# 50k-celebration-pcb.net
KiCad netlist of a schematic drawn in EAGLE
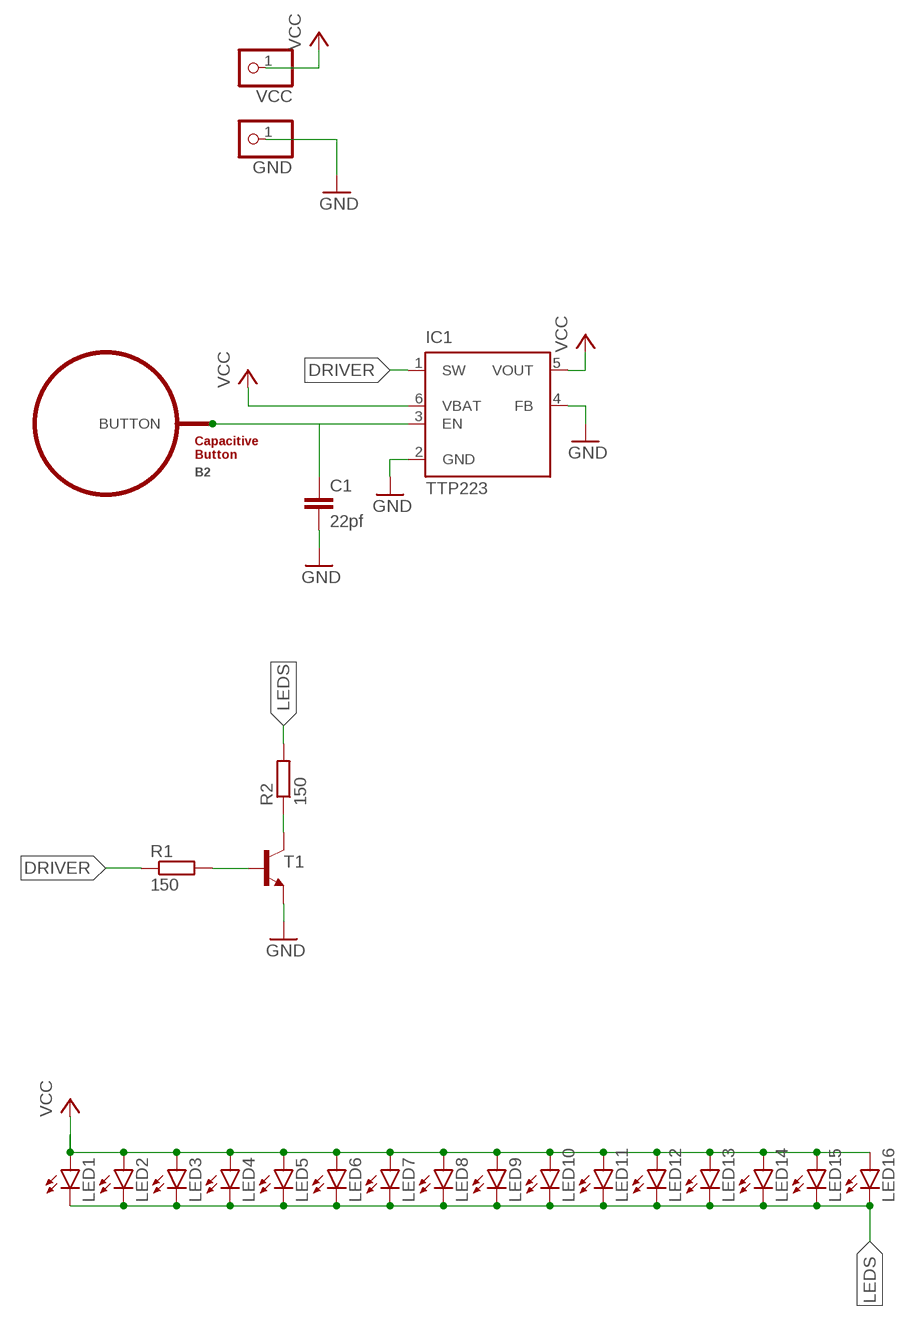
[diagram p0: schematic, sheet 1]

(export (version "E")
  (design (tool "Eeschema 10.0.6"))
  (components
    (comp (ref "B2")
      (value "BUTTON_PASSIVE8MM")
      (footprint "eagle-import:BUTTON_PASSIVE_8MM")
      (libsource (lib "eagle-import") (part "BUTTON_PASSIVE8MM"))
    )
    (comp (ref "C1")
      (value "22pf")
      (footprint "eagle-import:C0805")
      (libsource (lib "eagle-import") (part "C-EUC0805"))
    )
    (comp (ref "GND")
      (value "WPAD-1-SQ-0.5MM")
      (footprint "eagle-import:WPAD-1-SQ-0.5MM")
      (libsource (lib "eagle-import") (part "WPAD-1-SQ-0.5MM"))
    )
    (comp (ref "IC1")
      (value "TTP223")
      (footprint "eagle-import:TSOT23-6_DDC")
      (fields (field (name "MPN") "TPS61070DDCR"))
      (libsource (lib "eagle-import") (part "TPS6107DDC0"))
    )
    (comp (ref "LED1")
      (value "LEDCHIP-LED0805")
      (footprint "eagle-import:CHIP-LED0805")
      (libsource (lib "eagle-import") (part "LEDCHIP-LED0805"))
    )
    (comp (ref "LED2")
      (value "LEDCHIP-LED0805")
      (footprint "eagle-import:CHIP-LED0805")
      (libsource (lib "eagle-import") (part "LEDCHIP-LED0805"))
    )
    (comp (ref "LED3")
      (value "LEDCHIP-LED0805")
      (footprint "eagle-import:CHIP-LED0805")
      (libsource (lib "eagle-import") (part "LEDCHIP-LED0805"))
    )
    (comp (ref "LED4")
      (value "LEDCHIP-LED0805")
      (footprint "eagle-import:CHIP-LED0805")
      (libsource (lib "eagle-import") (part "LEDCHIP-LED0805"))
    )
    (comp (ref "LED5")
      (value "LEDCHIP-LED0805")
      (footprint "eagle-import:CHIP-LED0805")
      (libsource (lib "eagle-import") (part "LEDCHIP-LED0805"))
    )
    (comp (ref "LED6")
      (value "LEDCHIP-LED0805")
      (footprint "eagle-import:CHIP-LED0805")
      (libsource (lib "eagle-import") (part "LEDCHIP-LED0805"))
    )
    (comp (ref "LED7")
      (value "LEDCHIP-LED0805")
      (footprint "eagle-import:CHIP-LED0805")
      (libsource (lib "eagle-import") (part "LEDCHIP-LED0805"))
    )
    (comp (ref "LED8")
      (value "LEDCHIP-LED0805")
      (footprint "eagle-import:CHIP-LED0805")
      (libsource (lib "eagle-import") (part "LEDCHIP-LED0805"))
    )
    (comp (ref "LED9")
      (value "LEDCHIP-LED0805")
      (footprint "eagle-import:CHIP-LED0805")
      (libsource (lib "eagle-import") (part "LEDCHIP-LED0805"))
    )
    (comp (ref "LED10")
      (value "LEDCHIP-LED0805")
      (footprint "eagle-import:CHIP-LED0805")
      (libsource (lib "eagle-import") (part "LEDCHIP-LED0805"))
    )
    (comp (ref "LED11")
      (value "LEDCHIP-LED0805")
      (footprint "eagle-import:CHIP-LED0805")
      (libsource (lib "eagle-import") (part "LEDCHIP-LED0805"))
    )
    (comp (ref "LED12")
      (value "LEDCHIP-LED0805")
      (footprint "eagle-import:CHIP-LED0805")
      (libsource (lib "eagle-import") (part "LEDCHIP-LED0805"))
    )
    (comp (ref "LED13")
      (value "LEDCHIP-LED0805")
      (footprint "eagle-import:CHIP-LED0805")
      (libsource (lib "eagle-import") (part "LEDCHIP-LED0805"))
    )
    (comp (ref "LED14")
      (value "LEDCHIP-LED0805")
      (footprint "eagle-import:CHIP-LED0805")
      (libsource (lib "eagle-import") (part "LEDCHIP-LED0805"))
    )
    (comp (ref "LED15")
      (value "LEDCHIP-LED0805")
      (footprint "eagle-import:CHIP-LED0805")
      (libsource (lib "eagle-import") (part "LEDCHIP-LED0805"))
    )
    (comp (ref "LED16")
      (value "LEDCHIP-LED0805")
      (footprint "eagle-import:CHIP-LED0805")
      (libsource (lib "eagle-import") (part "LEDCHIP-LED0805"))
    )
    (comp (ref "R1")
      (value "150")
      (footprint "eagle-import:M0805")
      (libsource (lib "eagle-import") (part "R-EU_M0805"))
    )
    (comp (ref "R2")
      (value "150")
      (footprint "eagle-import:M0805")
      (libsource (lib "eagle-import") (part "R-EU_M0805"))
    )
    (comp (ref "T1")
      (value "BC817-16LT1-NPN-SOT23-BEC")
      (footprint "eagle-import:SOT23-BEC")
      (libsource (lib "eagle-import") (part "-NPN-SOT23-BECBC817-16LT1"))
    )
    (comp (ref "VCC")
      (value "WPAD-1-SQ-0.5MM")
      (footprint "eagle-import:WPAD-1-SQ-0.5MM")
      (libsource (lib "eagle-import") (part "WPAD-1-SQ-0.5MM"))
    )
  )
  (nets
    (net (code "1") (name "DRIVER") (class "Default")
      (node (ref "IC1") (pin "1") (pinfunction "SW_1") (pintype "input"))
      (node (ref "R1") (pin "1") (pinfunction "1_1") (pintype "passive"))
    )
    (net (code "2") (name "GND") (class "Default")
      (node (ref "C1") (pin "2") (pinfunction "2_2") (pintype "passive"))
      (node (ref "GND") (pin "1") (pinfunction "1_1") (pintype "passive"))
      (node (ref "IC1") (pin "2") (pinfunction "GND_2") (pintype "power_in"))
      (node (ref "IC1") (pin "4") (pinfunction "FB_4") (pintype "input"))
      (node (ref "T1") (pin "E") (pinfunction "E_E") (pintype "passive"))
    )
    (net (code "3") (name "LEDS") (class "Default")
      (node (ref "LED1") (pin "C") (pinfunction "C_C") (pintype "passive"))
      (node (ref "LED10") (pin "C") (pinfunction "C_C") (pintype "passive"))
      (node (ref "LED11") (pin "C") (pinfunction "C_C") (pintype "passive"))
      (node (ref "LED12") (pin "C") (pinfunction "C_C") (pintype "passive"))
      (node (ref "LED13") (pin "C") (pinfunction "C_C") (pintype "passive"))
      (node (ref "LED14") (pin "C") (pinfunction "C_C") (pintype "passive"))
      (node (ref "LED15") (pin "C") (pinfunction "C_C") (pintype "passive"))
      (node (ref "LED16") (pin "C") (pinfunction "C_C") (pintype "passive"))
      (node (ref "LED2") (pin "C") (pinfunction "C_C") (pintype "passive"))
      (node (ref "LED3") (pin "C") (pinfunction "C_C") (pintype "passive"))
      (node (ref "LED4") (pin "C") (pinfunction "C_C") (pintype "passive"))
      (node (ref "LED5") (pin "C") (pinfunction "C_C") (pintype "passive"))
      (node (ref "LED6") (pin "C") (pinfunction "C_C") (pintype "passive"))
      (node (ref "LED7") (pin "C") (pinfunction "C_C") (pintype "passive"))
      (node (ref "LED8") (pin "C") (pinfunction "C_C") (pintype "passive"))
      (node (ref "LED9") (pin "C") (pinfunction "C_C") (pintype "passive"))
      (node (ref "R2") (pin "2") (pinfunction "2_2") (pintype "passive"))
    )
    (net (code "4") (name "Net-(IC1-EN)") (class "Default")
      (node (ref "B2") (pin "BUTTON") (pinfunction "BUTTON_BUTTON") (pintype "passive"))
      (node (ref "C1") (pin "1") (pinfunction "1_1") (pintype "passive"))
      (node (ref "IC1") (pin "3") (pinfunction "EN_3") (pintype "input"))
    )
    (net (code "5") (name "Net-(R1-Pad2)") (class "Default")
      (node (ref "R1") (pin "2") (pinfunction "2_2") (pintype "passive"))
      (node (ref "T1") (pin "B") (pinfunction "B_B") (pintype "passive"))
    )
    (net (code "6") (name "Net-(R2-Pad1)") (class "Default")
      (node (ref "R2") (pin "1") (pinfunction "1_1") (pintype "passive"))
      (node (ref "T1") (pin "C") (pinfunction "C_C") (pintype "passive"))
    )
    (net (code "7") (name "VCC") (class "Default")
      (node (ref "IC1") (pin "5") (pinfunction "VOUT_5") (pintype "passive"))
      (node (ref "IC1") (pin "6") (pinfunction "VBAT_6") (pintype "input"))
      (node (ref "LED1") (pin "A") (pinfunction "A_A") (pintype "passive"))
      (node (ref "LED10") (pin "A") (pinfunction "A_A") (pintype "passive"))
      (node (ref "LED11") (pin "A") (pinfunction "A_A") (pintype "passive"))
      (node (ref "LED12") (pin "A") (pinfunction "A_A") (pintype "passive"))
      (node (ref "LED13") (pin "A") (pinfunction "A_A") (pintype "passive"))
      (node (ref "LED14") (pin "A") (pinfunction "A_A") (pintype "passive"))
      (node (ref "LED15") (pin "A") (pinfunction "A_A") (pintype "passive"))
      (node (ref "LED16") (pin "A") (pinfunction "A_A") (pintype "passive"))
      (node (ref "LED2") (pin "A") (pinfunction "A_A") (pintype "passive"))
      (node (ref "LED3") (pin "A") (pinfunction "A_A") (pintype "passive"))
      (node (ref "LED4") (pin "A") (pinfunction "A_A") (pintype "passive"))
      (node (ref "LED5") (pin "A") (pinfunction "A_A") (pintype "passive"))
      (node (ref "LED6") (pin "A") (pinfunction "A_A") (pintype "passive"))
      (node (ref "LED7") (pin "A") (pinfunction "A_A") (pintype "passive"))
      (node (ref "LED8") (pin "A") (pinfunction "A_A") (pintype "passive"))
      (node (ref "LED9") (pin "A") (pinfunction "A_A") (pintype "passive"))
      (node (ref "VCC") (pin "1") (pinfunction "1_1") (pintype "passive"))
    )
  )
)
